# untitled.net
KiCad netlist of a schematic drawn in EAGLE
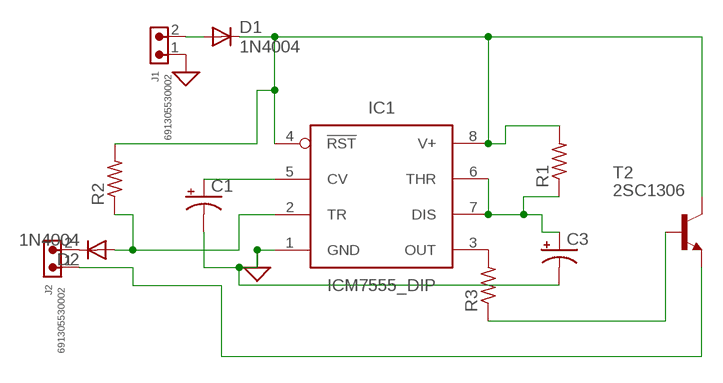
[diagram p0: schematic, sheet 1]

(export (version "E")
  (design (tool "Eeschema 10.0.6"))
  (components
    (comp (ref "C1")
      (value "CAPACITOR-PE2.5-5")
      (footprint "eagle-import:E2,5-5")
      (libsource (lib "eagle-import") (part "CAPACITOR-PE2.5-5"))
    )
    (comp (ref "C3")
      (value "CAPACITOR-PE2.5-5")
      (footprint "eagle-import:E2,5-5")
      (libsource (lib "eagle-import") (part "CAPACITOR-PE2.5-5"))
    )
    (comp (ref "D1")
      (value "1N4004")
      (footprint "eagle-import:DO41-10")
      (libsource (lib "eagle-import") (part "1N4004"))
    )
    (comp (ref "D2")
      (value "1N4004")
      (footprint "eagle-import:DO41-10")
      (libsource (lib "eagle-import") (part "1N4004"))
    )
    (comp (ref "IC1")
      (value "ICM7555_DIP")
      (footprint "eagle-import:DIP826W53P254L959H508Q8B")
      (fields
        (field (name "MANUFACTURER") "Renesas Electronics America Inc ")
        (field (name "MPN") "ICM7555IPAZ ")
      )
      (libsource (lib "eagle-import") (part "555_DIPICM7"))
    )
    (comp (ref "J1")
      (value "691305530002")
      (footprint "eagle-import:691305530002")
      (libsource (lib "eagle-import") (part "691305530002"))
    )
    (comp (ref "J2")
      (value "691305530002")
      (footprint "eagle-import:691305530002")
      (libsource (lib "eagle-import") (part "691305530002"))
    )
    (comp (ref "R1")
      (value "R-US_0207/7")
      (footprint "eagle-import:0207_7")
      (libsource (lib "eagle-import") (part "R-US_0207/7"))
    )
    (comp (ref "R2")
      (value "R-US_0207/7")
      (footprint "eagle-import:0207_7")
      (libsource (lib "eagle-import") (part "R-US_0207/7"))
    )
    (comp (ref "R3")
      (value "R-US_0207/7")
      (footprint "eagle-import:0207_7")
      (libsource (lib "eagle-import") (part "R-US_0207/7"))
    )
    (comp (ref "T2")
      (value "2SC1306")
      (footprint "eagle-import:TO220BV")
      (libsource (lib "eagle-import") (part "2SC1306"))
    )
  )
  (nets
    (net (code "1") (name "Net-(D1-PadA)") (class "Default")
      (node (ref "D1") (pin "A") (pinfunction "A_A") (pintype "passive"))
      (node (ref "J1") (pin "2") (pinfunction "2_2") (pintype "passive"))
    )
    (net (code "2") (name "Net-(D2-PadC)") (class "Default")
      (node (ref "D2") (pin "C") (pinfunction "C_C") (pintype "passive"))
      (node (ref "J2") (pin "2") (pinfunction "2_2") (pintype "passive"))
    )
    (net (code "3") (name "Net-(IC1-CV)") (class "Default")
      (node (ref "C1") (pin "+") (pinfunction "+_+") (pintype "passive"))
      (node (ref "IC1") (pin "5") (pinfunction "CV_5") (pintype "input"))
    )
    (net (code "4") (name "Net-(IC1-DIS)") (class "Default")
      (node (ref "C3") (pin "+") (pinfunction "+_+") (pintype "passive"))
      (node (ref "IC1") (pin "6") (pinfunction "THR_6") (pintype "input"))
      (node (ref "IC1") (pin "7") (pinfunction "DIS_7") (pintype "input"))
      (node (ref "R1") (pin "1") (pinfunction "1_1") (pintype "passive"))
    )
    (net (code "5") (name "Net-(IC1-OUT)") (class "Default")
      (node (ref "IC1") (pin "3") (pinfunction "OUT_3") (pintype "output"))
      (node (ref "R3") (pin "2") (pinfunction "2_2") (pintype "passive"))
    )
    (net (code "6") (name "Net-(IC1-TR)") (class "Default")
      (node (ref "D2") (pin "A") (pinfunction "A_A") (pintype "passive"))
      (node (ref "IC1") (pin "2") (pinfunction "TR_2") (pintype "input"))
      (node (ref "R2") (pin "1") (pinfunction "1_1") (pintype "passive"))
    )
    (net (code "7") (name "Net-(IC1-V+)") (class "Default")
      (node (ref "D1") (pin "C") (pinfunction "C_C") (pintype "passive"))
      (node (ref "IC1") (pin "4") (pinfunction "~{RST}_4") (pintype "input"))
      (node (ref "IC1") (pin "8") (pinfunction "V+_8") (pintype "power_in"))
      (node (ref "R1") (pin "2") (pinfunction "2_2") (pintype "passive"))
      (node (ref "R2") (pin "2") (pinfunction "2_2") (pintype "passive"))
      (node (ref "T2") (pin "2") (pinfunction "C_2") (pintype "passive"))
    )
    (net (code "8") (name "Net-(T2-B)") (class "Default")
      (node (ref "R3") (pin "1") (pinfunction "1_1") (pintype "passive"))
      (node (ref "T2") (pin "1") (pinfunction "B_1") (pintype "passive"))
    )
    (net (code "9") (name "Net-(T2-E)") (class "Default")
      (node (ref "J2") (pin "1") (pinfunction "1_1") (pintype "passive"))
      (node (ref "T2") (pin "3") (pinfunction "E_3") (pintype "passive"))
    )
    (net (code "10") (name "SUP") (class "Default")
      (node (ref "C1") (pin "-") (pinfunction "-_-") (pintype "passive"))
      (node (ref "C3") (pin "-") (pinfunction "-_-") (pintype "passive"))
      (node (ref "IC1") (pin "1") (pinfunction "GND_1") (pintype "power_in"))
      (node (ref "J1") (pin "1") (pinfunction "1_1") (pintype "passive"))
    )
  )
)
